# TOP.net
KiCad netlist of a schematic drawn in Altium Designer
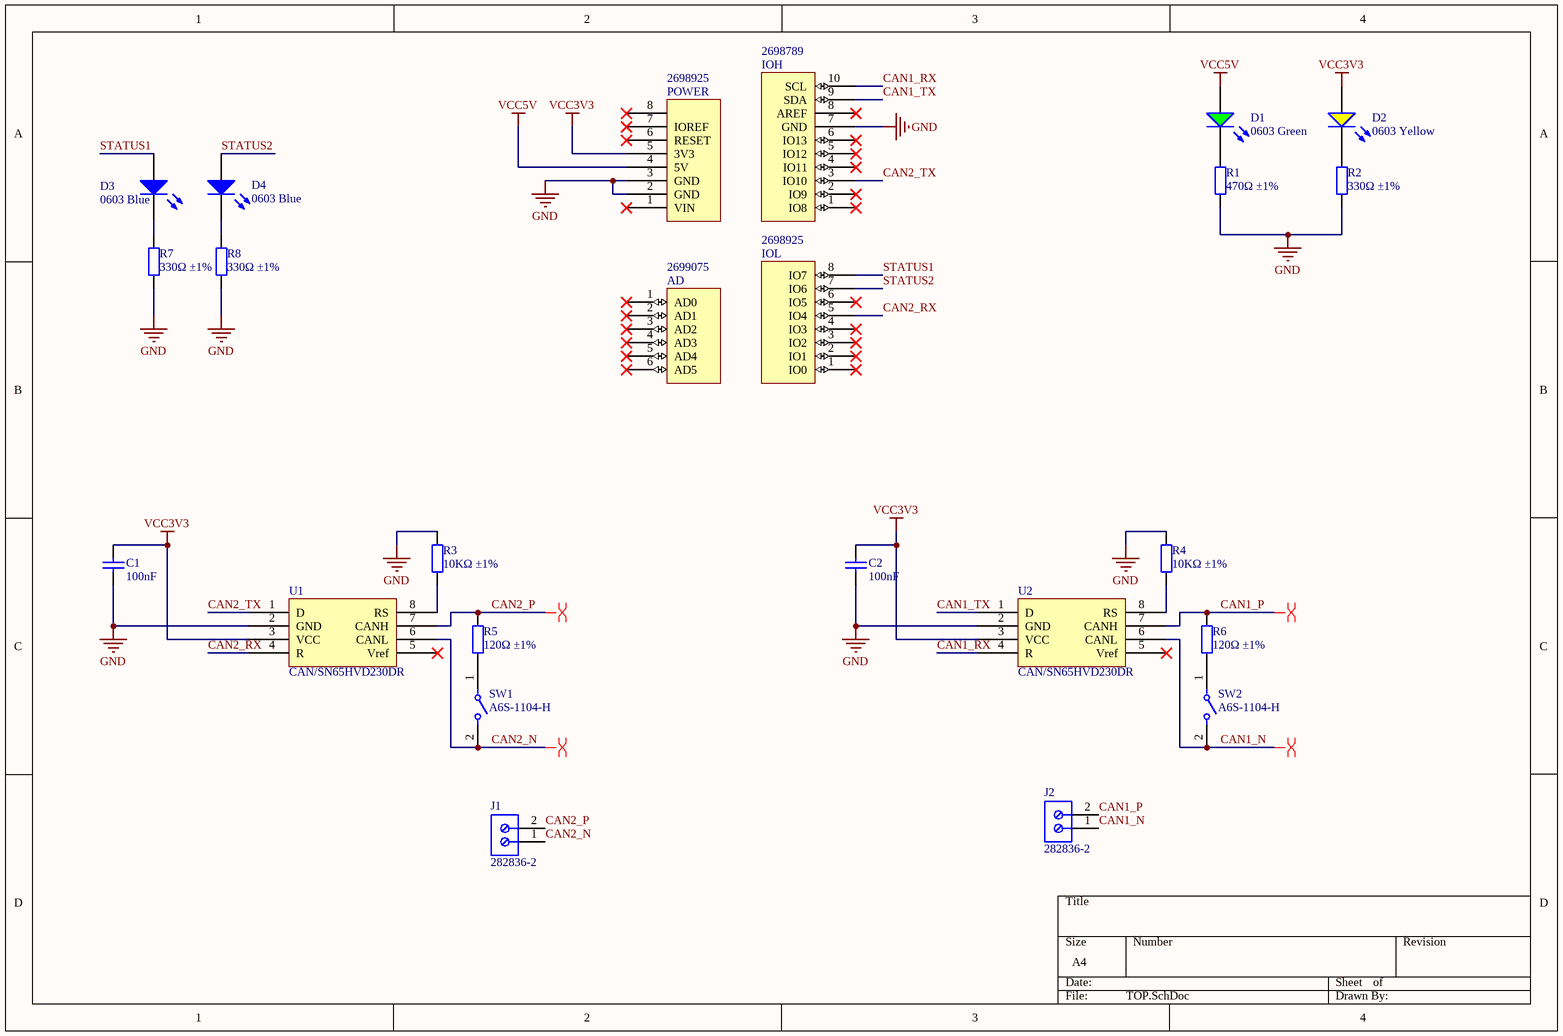
[diagram p0: TOP.SchDoc]

(export (version "E")
  (design (tool "Eeschema 10.0.6"))
  (components
    (comp (ref "AD")
      (value "AD")
      (footprint "Header:Header 6x1 8.5mm")
      (fields (field (name "SUPPLIER PART NUMBER 4") "2699075"))
      (libsource (lib "Header") (part "AD"))
    )
    (comp (ref "C1")
      (value "100nF")
      (footprint "0402_C")
      (description "Chip capacitors")
      (fields
        (field (name "MANUFACTURER") "Samsung Electro-Mechanics")
        (field (name "PARTNUMBER") "CL05B104KO5NNNC")
      )
      (libsource (lib "Miscellaneous Devices LC") (part "0402 100nF (104) 10% 16V"))
    )
    (comp (ref "C2")
      (value "100nF")
      (footprint "0402_C")
      (description "Chip capacitors")
      (fields
        (field (name "MANUFACTURER") "Samsung Electro-Mechanics")
        (field (name "PARTNUMBER") "CL05B104KO5NNNC")
      )
      (libsource (lib "Miscellaneous Devices LC") (part "0402 100nF (104) 10% 16V"))
    )
    (comp (ref "D1")
      (value "0603 Green")
      (footprint "0603_LED_S1")
      (description "LED")
      (libsource (lib "Miscellaneous Devices LC") (part "0603 LED Green"))
    )
    (comp (ref "D2")
      (value "0603 Yellow")
      (footprint "0603_LED_S1")
      (description "LED")
      (libsource (lib "Miscellaneous Devices LC") (part "0603 LED Yellow"))
    )
    (comp (ref "D3")
      (value "0603 Blue")
      (footprint "0603_LED_S1")
      (description "LED")
      (libsource (lib "Miscellaneous Devices LC") (part "0603 LED Blue"))
    )
    (comp (ref "D4")
      (value "0603 Blue")
      (footprint "0603_LED_S1")
      (description "LED")
      (libsource (lib "Miscellaneous Devices LC") (part "0603 LED Blue"))
    )
    (comp (ref "IOH")
      (value "IOH")
      (footprint "Header:Header 10x1 8.5mm")
      (fields (field (name "SUPPLIER PART NUMBER 3") "2698789"))
      (libsource (lib "Header") (part "IOH"))
    )
    (comp (ref "IOL")
      (value "IOL")
      (footprint "Header 8x1 8.5mm")
      (fields (field (name "SUPPLIER PART NUMBER 4") "2698925"))
      (libsource (lib "Header") (part "IOL"))
    )
    (comp (ref "J1")
      (value "282836-2")
      (footprint "TECO-282836-2_V")
      (description "Female Header, Pitch 5 mm, 1 x 2 Position, Height 10 mm, Tail Length 3.5 mm, Rohs, Bulk")
      (fields (field (name "VOLTAGE") "300V") (field (name "MANUFACTURER") "TE Connectivity"))
      (libsource (lib "Altium Content Vault") (part "CN-1P-F-TB2"))
    )
    (comp (ref "J2")
      (value "282836-2")
      (footprint "TECO-282836-2_V")
      (description "Female Header, Pitch 5 mm, 1 x 2 Position, Height 10 mm, Tail Length 3.5 mm, Rohs, Bulk")
      (fields (field (name "VOLTAGE") "300V") (field (name "MANUFACTURER") "TE Connectivity"))
      (libsource (lib "Altium Content Vault") (part "CN-1P-F-TB2"))
    )
    (comp (ref "POWER")
      (value "POWER_UNO")
      (footprint "Header 8x1 8.5mm")
      (fields (field (name "SUPPLIER PART NUMBER 4") "2698925"))
      (libsource (lib "Header") (part "POWER_UNO"))
    )
    (comp (ref "R1")
      (value "470Ω ±1%")
      (footprint "0402_R")
      (description "Chip resistor")
      (fields (field (name "MANUFACTURER") "Uniroyal Elec") (field (name "PARTNUMBER") "0402WGF4700TCE"))
      (libsource (lib "Miscellaneous Devices LC") (part "0402 470R (4700) 1%"))
    )
    (comp (ref "R2")
      (value "330Ω ±1%")
      (footprint "0402_R")
      (description "Chip resistor")
      (fields (field (name "MANUFACTURER") "Uniroyal Elec") (field (name "PARTNUMBER") "0402WGF3300TCE"))
      (libsource (lib "Miscellaneous Devices LC") (part "0402 330R (3300) 1%"))
    )
    (comp (ref "R3")
      (value "10KΩ ±1%")
      (footprint "0402_R")
      (description "Chip resistor")
      (fields (field (name "MANUFACTURER") "Uniroyal Elec") (field (name "PARTNUMBER") "0402WGF1002TCE"))
      (libsource (lib "Miscellaneous Devices LC") (part "0402 10K (1002) 1%"))
    )
    (comp (ref "R4")
      (value "10KΩ ±1%")
      (footprint "0402_R")
      (description "Chip resistor")
      (fields (field (name "MANUFACTURER") "Uniroyal Elec") (field (name "PARTNUMBER") "0402WGF1002TCE"))
      (libsource (lib "Miscellaneous Devices LC") (part "0402 10K (1002) 1%"))
    )
    (comp (ref "R5")
      (value "120Ω ±1%")
      (footprint "0402_R")
      (description "Chip resistor")
      (fields (field (name "MANUFACTURER") "Uniroyal Elec") (field (name "PARTNUMBER") "0402WGF1200TCE"))
      (libsource (lib "Miscellaneous Devices LC") (part "0402 120R (1200) 1%"))
    )
    (comp (ref "R6")
      (value "120Ω ±1%")
      (footprint "0402_R")
      (description "Chip resistor")
      (fields (field (name "MANUFACTURER") "Uniroyal Elec") (field (name "PARTNUMBER") "0402WGF1200TCE"))
      (libsource (lib "Miscellaneous Devices LC") (part "0402 120R (1200) 1%"))
    )
    (comp (ref "R7")
      (value "330Ω ±1%")
      (footprint "0402_R")
      (description "Chip resistor")
      (fields (field (name "MANUFACTURER") "Uniroyal Elec") (field (name "PARTNUMBER") "0402WGF3300TCE"))
      (libsource (lib "Miscellaneous Devices LC") (part "0402 330R (3300) 1%"))
    )
    (comp (ref "R8")
      (value "330Ω ±1%")
      (footprint "0402_R")
      (description "Chip resistor")
      (fields (field (name "MANUFACTURER") "Uniroyal Elec") (field (name "PARTNUMBER") "0402WGF3300TCE"))
      (libsource (lib "Miscellaneous Devices LC") (part "0402 330R (3300) 1%"))
    )
    (comp (ref "SW1")
      (value "A6S-1104-H")
      (footprint "FP-A6S-1104-H-MFG")
      (description "SWITCH SLIDE DIP SPST 25MA 24V")
      (fields
        (field (name "MANUFACTURER") "Omron Electronics Inc-EMC Div")
        (field (name "OCTOPART") "https://octopart.com/a6s-1104-h-omron-55410938")
      )
      (libsource (lib "Altium Content Vault") (part "bb27bde45df87f1f469753f287ef5ae"))
    )
    (comp (ref "SW2")
      (value "A6S-1104-H")
      (footprint "FP-A6S-1104-H-MFG")
      (description "SWITCH SLIDE DIP SPST 25MA 24V")
      (fields
        (field (name "MANUFACTURER") "Omron Electronics Inc-EMC Div")
        (field (name "OCTOPART") "https://octopart.com/a6s-1104-h-omron-55410938")
      )
      (libsource (lib "Altium Content Vault") (part "bb27bde45df87f1f469753f287ef5ae"))
    )
    (comp (ref "U1")
      (value "CAN/SN65HVD230DR")
      (footprint "SOIC-8_150mil")
      (description "CAN")
      (libsource (lib "Miscellaneous Devices LC") (part "CAN/SN65HVD230DR_[C12084]"))
    )
    (comp (ref "U2")
      (value "CAN/SN65HVD230DR")
      (footprint "SOIC-8_150mil")
      (description "CAN")
      (libsource (lib "Miscellaneous Devices LC") (part "CAN/SN65HVD230DR_[C12084]"))
    )
  )
  (nets
    (net (code "2") (name "/CAN1_N") (class "Default")
      (node (ref "J2") (pin "1") (pinfunction "1_1") (pintype "passive"))
      (node (ref "SW2") (pin "2") (pinfunction "2_2") (pintype "passive"))
      (node (ref "U2") (pin "6") (pinfunction "CANL_6") (pintype "passive"))
    )
    (net (code "3") (name "/CAN1_P") (class "Default")
      (node (ref "J2") (pin "2") (pinfunction "2_2") (pintype "passive"))
      (node (ref "R6") (pin "2") (pinfunction "2_2") (pintype "passive"))
      (node (ref "U2") (pin "7") (pinfunction "CANH_7") (pintype "passive"))
    )
    (net (code "4") (name "/CAN1_RX") (class "Default")
      (node (ref "IOH") (pin "10") (pinfunction "SCL_10") (pintype "bidirectional"))
      (node (ref "U2") (pin "4") (pinfunction "R_4") (pintype "passive"))
    )
    (net (code "5") (name "/CAN1_TX") (class "Default")
      (node (ref "IOH") (pin "9") (pinfunction "SDA_9") (pintype "bidirectional"))
      (node (ref "U2") (pin "1") (pinfunction "D_1") (pintype "passive"))
    )
    (net (code "6") (name "/CAN2_N") (class "Default")
      (node (ref "J1") (pin "1") (pinfunction "1_1") (pintype "passive"))
      (node (ref "SW1") (pin "2") (pinfunction "2_2") (pintype "passive"))
      (node (ref "U1") (pin "6") (pinfunction "CANL_6") (pintype "passive"))
    )
    (net (code "7") (name "/CAN2_P") (class "Default")
      (node (ref "J1") (pin "2") (pinfunction "2_2") (pintype "passive"))
      (node (ref "R5") (pin "2") (pinfunction "2_2") (pintype "passive"))
      (node (ref "U1") (pin "7") (pinfunction "CANH_7") (pintype "passive"))
    )
    (net (code "8") (name "/CAN2_RX") (class "Default")
      (node (ref "IOL") (pin "5") (pinfunction "IO4_5") (pintype "bidirectional"))
      (node (ref "U1") (pin "4") (pinfunction "R_4") (pintype "passive"))
    )
    (net (code "9") (name "/CAN2_TX") (class "Default")
      (node (ref "IOH") (pin "3") (pinfunction "IO10_3") (pintype "bidirectional"))
      (node (ref "U1") (pin "1") (pinfunction "D_1") (pintype "passive"))
    )
    (net (code "10") (name "/STATUS1") (class "Default")
      (node (ref "D3") (pin "A") (pinfunction "A_A") (pintype "passive"))
      (node (ref "IOL") (pin "8") (pinfunction "IO7_8") (pintype "bidirectional"))
    )
    (net (code "11") (name "/STATUS2") (class "Default")
      (node (ref "D4") (pin "A") (pinfunction "A_A") (pintype "passive"))
      (node (ref "IOL") (pin "7") (pinfunction "IO6_7") (pintype "bidirectional"))
    )
    (net (code "12") (name "GND") (class "Default")
      (node (ref "C1") (pin "1") (pinfunction "1_1") (pintype "passive"))
      (node (ref "C2") (pin "1") (pinfunction "1_1") (pintype "passive"))
      (node (ref "IOH") (pin "7") (pinfunction "GND_7") (pintype "power_in"))
      (node (ref "POWER") (pin "2") (pinfunction "GND_2") (pintype "power_in"))
      (node (ref "POWER") (pin "3") (pinfunction "GND_3") (pintype "power_in"))
      (node (ref "R1") (pin "2") (pinfunction "2_2") (pintype "passive"))
      (node (ref "R2") (pin "1") (pinfunction "1_1") (pintype "passive"))
      (node (ref "R3") (pin "2") (pinfunction "2_2") (pintype "passive"))
      (node (ref "R4") (pin "2") (pinfunction "2_2") (pintype "passive"))
      (node (ref "R7") (pin "1") (pinfunction "1_1") (pintype "passive"))
      (node (ref "R8") (pin "1") (pinfunction "1_1") (pintype "passive"))
      (node (ref "U1") (pin "2") (pinfunction "GND_2") (pintype "passive"))
      (node (ref "U2") (pin "2") (pinfunction "GND_2") (pintype "passive"))
    )
    (net (code "13") (name "Net-(D1-PadK)") (class "Default")
      (node (ref "D1") (pin "K") (pinfunction "K_K") (pintype "passive"))
      (node (ref "R1") (pin "1") (pinfunction "1_1") (pintype "passive"))
    )
    (net (code "14") (name "Net-(D2-PadK)") (class "Default")
      (node (ref "D2") (pin "K") (pinfunction "K_K") (pintype "passive"))
      (node (ref "R2") (pin "2") (pinfunction "2_2") (pintype "passive"))
    )
    (net (code "15") (name "Net-(D3-PadK)") (class "Default")
      (node (ref "D3") (pin "K") (pinfunction "K_K") (pintype "passive"))
      (node (ref "R7") (pin "2") (pinfunction "2_2") (pintype "passive"))
    )
    (net (code "16") (name "Net-(D4-PadK)") (class "Default")
      (node (ref "D4") (pin "K") (pinfunction "K_K") (pintype "passive"))
      (node (ref "R8") (pin "2") (pinfunction "2_2") (pintype "passive"))
    )
    (net (code "17") (name "Net-(R5-Pad1)") (class "Default")
      (node (ref "R5") (pin "1") (pinfunction "1_1") (pintype "passive"))
      (node (ref "SW1") (pin "1") (pinfunction "1_1") (pintype "passive"))
    )
    (net (code "18") (name "Net-(R6-Pad1)") (class "Default")
      (node (ref "R6") (pin "1") (pinfunction "1_1") (pintype "passive"))
      (node (ref "SW2") (pin "1") (pinfunction "1_1") (pintype "passive"))
    )
    (net (code "19") (name "Net-(U1-RS)") (class "Default")
      (node (ref "R3") (pin "1") (pinfunction "1_1") (pintype "passive"))
      (node (ref "U1") (pin "8") (pinfunction "RS_8") (pintype "passive"))
    )
    (net (code "20") (name "Net-(U2-RS)") (class "Default")
      (node (ref "R4") (pin "1") (pinfunction "1_1") (pintype "passive"))
      (node (ref "U2") (pin "8") (pinfunction "RS_8") (pintype "passive"))
    )
    (net (code "21") (name "VCC3V3") (class "Default")
      (node (ref "C1") (pin "2") (pinfunction "2_2") (pintype "passive"))
      (node (ref "C2") (pin "2") (pinfunction "2_2") (pintype "passive"))
      (node (ref "D2") (pin "A") (pinfunction "A_A") (pintype "passive"))
      (node (ref "POWER") (pin "5") (pinfunction "3V3_5") (pintype "power_in"))
      (node (ref "U1") (pin "3") (pinfunction "VCC_3") (pintype "passive"))
      (node (ref "U2") (pin "3") (pinfunction "VCC_3") (pintype "passive"))
    )
    (net (code "22") (name "VCC5V") (class "Default")
      (node (ref "D1") (pin "A") (pinfunction "A_A") (pintype "passive"))
      (node (ref "POWER") (pin "4") (pinfunction "5V_4") (pintype "power_in"))
    )
    (net (code "23") (name "unconnected-(AD-AD0-Pad1)") (class "Default")
      (node (ref "AD") (pin "1") (pinfunction "AD0_1") (pintype "bidirectional+no_connect"))
    )
    (net (code "24") (name "unconnected-(AD-AD1-Pad2)") (class "Default")
      (node (ref "AD") (pin "2") (pinfunction "AD1_2") (pintype "bidirectional+no_connect"))
    )
    (net (code "25") (name "unconnected-(AD-AD2-Pad3)") (class "Default")
      (node (ref "AD") (pin "3") (pinfunction "AD2_3") (pintype "bidirectional+no_connect"))
    )
    (net (code "26") (name "unconnected-(AD-AD3-Pad4)") (class "Default")
      (node (ref "AD") (pin "4") (pinfunction "AD3_4") (pintype "bidirectional+no_connect"))
    )
    (net (code "27") (name "unconnected-(AD-AD4-Pad5)") (class "Default")
      (node (ref "AD") (pin "5") (pinfunction "AD4_5") (pintype "bidirectional+no_connect"))
    )
    (net (code "28") (name "unconnected-(AD-AD5-Pad6)") (class "Default")
      (node (ref "AD") (pin "6") (pinfunction "AD5_6") (pintype "bidirectional+no_connect"))
    )
    (net (code "29") (name "unconnected-(IOH-AREF-Pad8)") (class "Default")
      (node (ref "IOH") (pin "8") (pinfunction "AREF_8") (pintype "passive+no_connect"))
    )
    (net (code "30") (name "unconnected-(IOH-IO8-Pad1)") (class "Default")
      (node (ref "IOH") (pin "1") (pinfunction "IO8_1") (pintype "bidirectional+no_connect"))
    )
    (net (code "31") (name "unconnected-(IOH-IO9-Pad2)") (class "Default")
      (node (ref "IOH") (pin "2") (pinfunction "IO9_2") (pintype "bidirectional+no_connect"))
    )
    (net (code "32") (name "unconnected-(IOH-IO11-Pad4)") (class "Default")
      (node (ref "IOH") (pin "4") (pinfunction "IO11_4") (pintype "bidirectional+no_connect"))
    )
    (net (code "33") (name "unconnected-(IOH-IO12-Pad5)") (class "Default")
      (node (ref "IOH") (pin "5") (pinfunction "IO12_5") (pintype "bidirectional+no_connect"))
    )
    (net (code "34") (name "unconnected-(IOH-IO13-Pad6)") (class "Default")
      (node (ref "IOH") (pin "6") (pinfunction "IO13_6") (pintype "bidirectional+no_connect"))
    )
    (net (code "35") (name "unconnected-(IOL-IO0-Pad1)") (class "Default")
      (node (ref "IOL") (pin "1") (pinfunction "IO0_1") (pintype "bidirectional+no_connect"))
    )
    (net (code "36") (name "unconnected-(IOL-IO1-Pad2)") (class "Default")
      (node (ref "IOL") (pin "2") (pinfunction "IO1_2") (pintype "bidirectional+no_connect"))
    )
    (net (code "37") (name "unconnected-(IOL-IO2-Pad3)") (class "Default")
      (node (ref "IOL") (pin "3") (pinfunction "IO2_3") (pintype "bidirectional+no_connect"))
    )
    (net (code "38") (name "unconnected-(IOL-IO3-Pad4)") (class "Default")
      (node (ref "IOL") (pin "4") (pinfunction "IO3_4") (pintype "bidirectional+no_connect"))
    )
    (net (code "39") (name "unconnected-(IOL-IO5-Pad6)") (class "Default")
      (node (ref "IOL") (pin "6") (pinfunction "IO5_6") (pintype "bidirectional+no_connect"))
    )
    (net (code "40") (name "unconnected-(POWER-IOREF-Pad7)") (class "Default")
      (node (ref "POWER") (pin "7") (pinfunction "IOREF_7") (pintype "power_in+no_connect"))
    )
    (net (code "41") (name "unconnected-(POWER-Pad8)") (class "Default")
      (node (ref "POWER") (pin "8") (pintype "passive+no_connect"))
    )
    (net (code "42") (name "unconnected-(POWER-RESET-Pad6)") (class "Default")
      (node (ref "POWER") (pin "6") (pinfunction "RESET_6") (pintype "passive+no_connect"))
    )
    (net (code "43") (name "unconnected-(POWER-VIN-Pad1)") (class "Default")
      (node (ref "POWER") (pin "1") (pinfunction "VIN_1") (pintype "power_in+no_connect"))
    )
    (net (code "44") (name "unconnected-(U1-Vref-Pad5)") (class "Default")
      (node (ref "U1") (pin "5") (pinfunction "Vref_5") (pintype "passive+no_connect"))
    )
    (net (code "45") (name "unconnected-(U2-Vref-Pad5)") (class "Default")
      (node (ref "U2") (pin "5") (pinfunction "Vref_5") (pintype "passive+no_connect"))
    )
  )
)
